# uInverter_02.net
KiCad netlist of a schematic drawn in Altium Designer
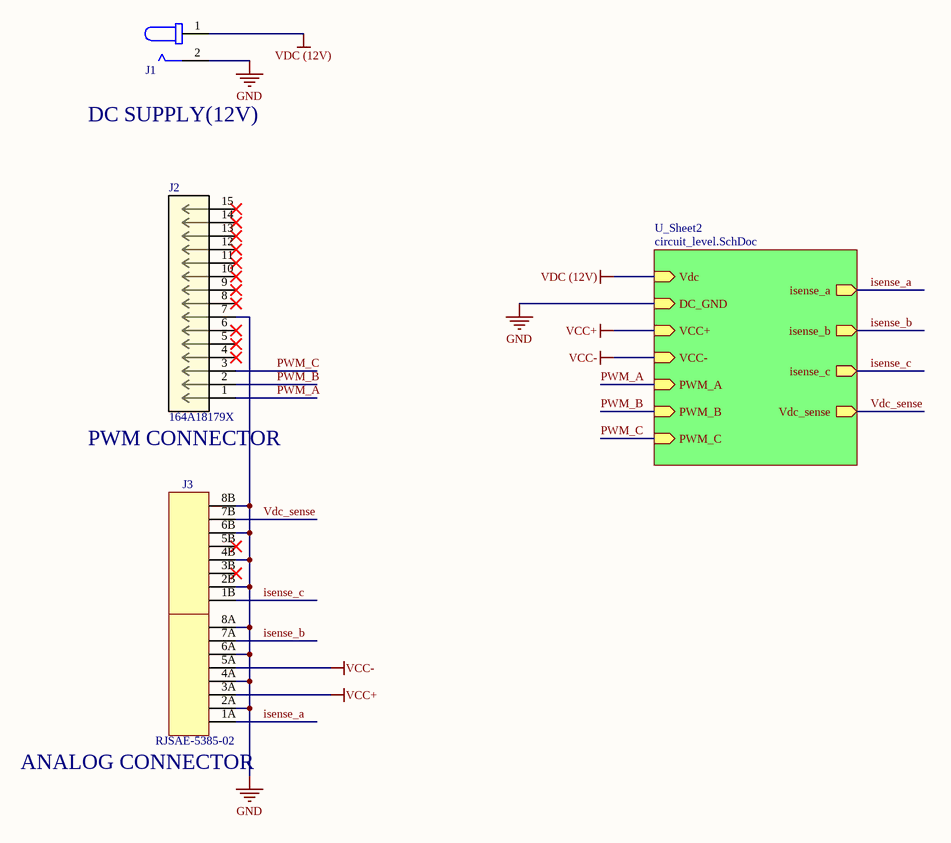
[diagram p0: uInverter_02.SchDoc]

(export (version "E")
  (design (tool "Eeschema 10.0.6"))
  (components
    (comp (ref "J1")
      (value "PJ-037AH")
      (description "CONN PWR JACK 2X5.5MM SOLDER")
      (fields (field (name "MANUFACTURER") "CUI"))
      (libsource (lib "Schlib_uInv01") (part "PJ-037AH"))
    )
    (comp (ref "J2")
      (value "164A18179X")
      (description "CONN DSUB HD RCPT 15POS R/A SLDR")
      (fields (field (name "MANUFACTURER") "Conec"))
      (libsource (lib "Schlib_uInv01") (part "164A18179X"))
    )
    (comp (ref "J3")
      (value "RJSAE-5385-02")
      (description "CONN MOD JACK 8P8C R/A SHIELDED")
      (fields (field (name "MANUFACTURER") "Amphenol Commercial"))
      (libsource (lib "Schlib_uInv01") (part "RJSAE-5385-02"))
    )
  )
  (nets
    (net (code "1") (name "/PWM_A") (class "Default")
      (node (ref "J2") (pin "1") (pinfunction "1_1") (pintype "passive"))
    )
    (net (code "2") (name "/PWM_B") (class "Default")
      (node (ref "J2") (pin "2") (pinfunction "2_2") (pintype "passive"))
    )
    (net (code "3") (name "/PWM_C") (class "Default")
      (node (ref "J2") (pin "3") (pinfunction "3_3") (pintype "passive"))
    )
    (net (code "4") (name "/Vdc_sense") (class "Default")
      (node (ref "J3") (pin "7B") (pinfunction "79_7B") (pintype "passive"))
    )
    (net (code "5") (name "/isense_a") (class "Default")
      (node (ref "J3") (pin "1A") (pinfunction "79_1A") (pintype "passive"))
    )
    (net (code "6") (name "/isense_b") (class "Default")
      (node (ref "J3") (pin "7A") (pinfunction "79_7A") (pintype "passive"))
    )
    (net (code "7") (name "/isense_c") (class "Default")
      (node (ref "J3") (pin "1B") (pinfunction "79_1B") (pintype "passive"))
    )
    (net (code "8") (name "GND") (class "Default")
      (node (ref "J1") (pin "2") (pinfunction "2_2") (pintype "passive"))
      (node (ref "J2") (pin "7") (pinfunction "7_7") (pintype "passive"))
      (node (ref "J3") (pin "2A") (pinfunction "79_2A") (pintype "passive"))
      (node (ref "J3") (pin "2B") (pinfunction "79_2B") (pintype "passive"))
      (node (ref "J3") (pin "4A") (pinfunction "79_4A") (pintype "passive"))
      (node (ref "J3") (pin "4B") (pinfunction "79_4B") (pintype "passive"))
      (node (ref "J3") (pin "6A") (pinfunction "79_6A") (pintype "passive"))
      (node (ref "J3") (pin "6B") (pinfunction "79_6B") (pintype "passive"))
      (node (ref "J3") (pin "8A") (pinfunction "79_8A") (pintype "passive"))
      (node (ref "J3") (pin "8B") (pinfunction "79_8B") (pintype "passive"))
    )
    (net (code "9") (name "VCC+") (class "Default")
      (node (ref "J3") (pin "3A") (pinfunction "79_3A") (pintype "passive"))
    )
    (net (code "10") (name "VCC-") (class "Default")
      (node (ref "J3") (pin "5A") (pinfunction "79_5A") (pintype "passive"))
    )
    (net (code "11") (name "VDC (12V)") (class "Default")
      (node (ref "J1") (pin "1") (pinfunction "1_1") (pintype "passive"))
    )
    (net (code "12") (name "unconnected-(J2-Pad4)") (class "Default")
      (node (ref "J2") (pin "4") (pinfunction "4_4") (pintype "passive+no_connect"))
    )
    (net (code "13") (name "unconnected-(J2-Pad5)") (class "Default")
      (node (ref "J2") (pin "5") (pinfunction "5_5") (pintype "passive+no_connect"))
    )
    (net (code "14") (name "unconnected-(J2-Pad6)") (class "Default")
      (node (ref "J2") (pin "6") (pinfunction "6_6") (pintype "passive+no_connect"))
    )
    (net (code "15") (name "unconnected-(J2-Pad8)") (class "Default")
      (node (ref "J2") (pin "8") (pinfunction "8_8") (pintype "passive+no_connect"))
    )
    (net (code "16") (name "unconnected-(J2-Pad9)") (class "Default")
      (node (ref "J2") (pin "9") (pinfunction "9_9") (pintype "passive+no_connect"))
    )
    (net (code "17") (name "unconnected-(J2-Pad10)") (class "Default")
      (node (ref "J2") (pin "10") (pinfunction "10_10") (pintype "passive+no_connect"))
    )
    (net (code "18") (name "unconnected-(J2-Pad11)") (class "Default")
      (node (ref "J2") (pin "11") (pinfunction "11_11") (pintype "passive+no_connect"))
    )
    (net (code "19") (name "unconnected-(J2-Pad12)") (class "Default")
      (node (ref "J2") (pin "12") (pinfunction "12_12") (pintype "passive+no_connect"))
    )
    (net (code "20") (name "unconnected-(J2-Pad13)") (class "Default")
      (node (ref "J2") (pin "13") (pinfunction "13_13") (pintype "passive+no_connect"))
    )
    (net (code "21") (name "unconnected-(J2-Pad14)") (class "Default")
      (node (ref "J2") (pin "14") (pinfunction "14_14") (pintype "passive+no_connect"))
    )
    (net (code "22") (name "unconnected-(J2-Pad15)") (class "Default")
      (node (ref "J2") (pin "15") (pinfunction "15_15") (pintype "passive+no_connect"))
    )
    (net (code "23") (name "unconnected-(J3-79-Pad3B)") (class "Default")
      (node (ref "J3") (pin "3B") (pinfunction "79_3B") (pintype "passive+no_connect"))
    )
    (net (code "24") (name "unconnected-(J3-79-Pad5B)") (class "Default")
      (node (ref "J3") (pin "5B") (pinfunction "79_5B") (pintype "passive+no_connect"))
    )
  )
)
